# Project1.net
KiCad netlist of a schematic drawn in EAGLE
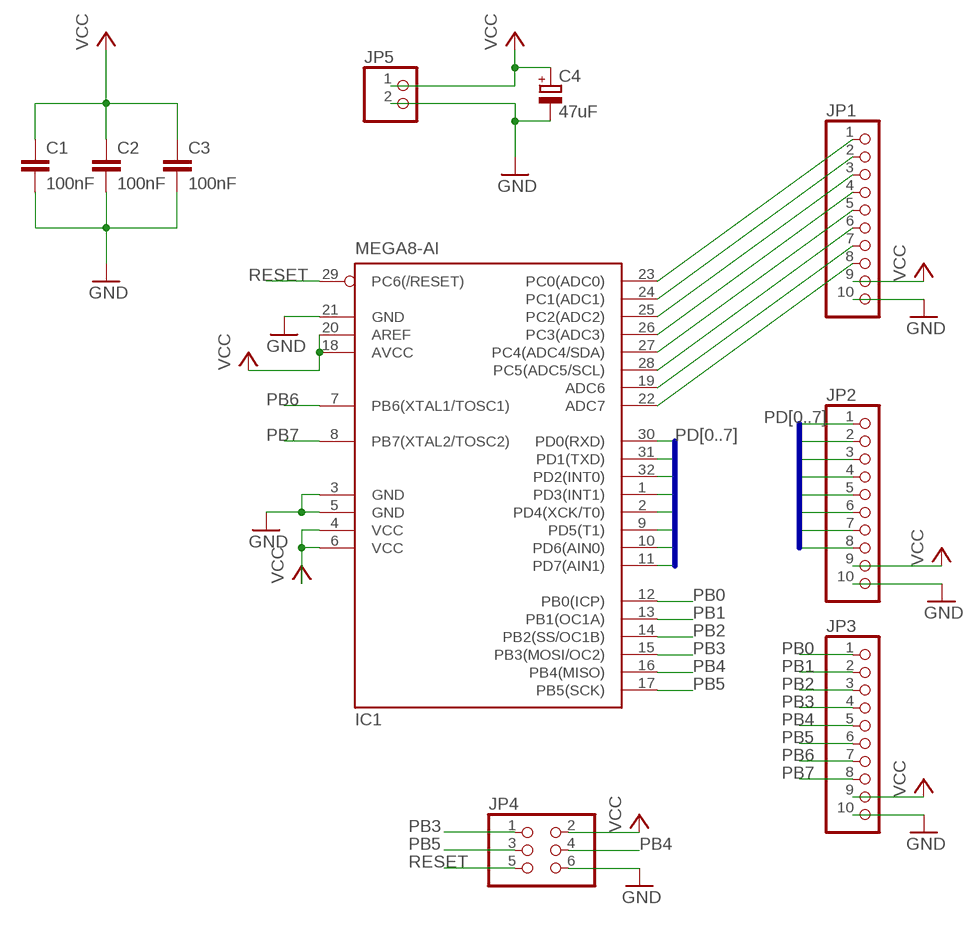
[diagram p0: schematic, sheet 1]

(export (version "E")
  (design (tool "Eeschema 10.0.6"))
  (components
    (comp (ref "C1")
      (value "100nF")
      (footprint "eagle-import:C0603")
      (libsource (lib "eagle-import") (part "C-EUC0603"))
    )
    (comp (ref "C2")
      (value "100nF")
      (footprint "eagle-import:C0603")
      (libsource (lib "eagle-import") (part "C-EUC0603"))
    )
    (comp (ref "C3")
      (value "100nF")
      (footprint "eagle-import:C0603")
      (libsource (lib "eagle-import") (part "C-EUC0603"))
    )
    (comp (ref "C4")
      (value "47uF")
      (footprint "eagle-import:E2,5-6")
      (libsource (lib "eagle-import") (part "CPOL-EUE2.5-6"))
    )
    (comp (ref "IC1")
      (value "MEGA8-AI")
      (footprint "eagle-import:TQFP32-08")
      (fields (field (name "MPN") "ATMEGA8-16AU"))
      (libsource (lib "eagle-import") (part "MEGA8-AI"))
    )
    (comp (ref "JP1")
      (value "PINHD-1X10")
      (footprint "eagle-import:1X10")
      (libsource (lib "eagle-import") (part "PINHD-1X10"))
    )
    (comp (ref "JP2")
      (value "PINHD-1X10")
      (footprint "eagle-import:1X10")
      (libsource (lib "eagle-import") (part "PINHD-1X10"))
    )
    (comp (ref "JP3")
      (value "PINHD-1X10")
      (footprint "eagle-import:1X10")
      (libsource (lib "eagle-import") (part "PINHD-1X10"))
    )
    (comp (ref "JP4")
      (value "PINHD-2X3")
      (footprint "eagle-import:2X03")
      (libsource (lib "eagle-import") (part "PINHD-2X3"))
    )
    (comp (ref "JP5")
      (value "PINHD-1X2")
      (footprint "eagle-import:1X02")
      (libsource (lib "eagle-import") (part "PINHD-1X2"))
    )
  )
  (nets
    (net (code "1") (name "/PB0") (class "Default")
      (node (ref "IC1") (pin "12") (pinfunction "PB0(ICP)_12") (pintype "bidirectional"))
      (node (ref "JP3") (pin "1") (pinfunction "1_1") (pintype "passive"))
    )
    (net (code "2") (name "/PB1") (class "Default")
      (node (ref "IC1") (pin "13") (pinfunction "PB1(OC1A)_13") (pintype "bidirectional"))
      (node (ref "JP3") (pin "2") (pinfunction "2_2") (pintype "passive"))
    )
    (net (code "3") (name "/PB2") (class "Default")
      (node (ref "IC1") (pin "14") (pinfunction "PB2(SS/OC1B)_14") (pintype "bidirectional"))
      (node (ref "JP3") (pin "3") (pinfunction "3_3") (pintype "passive"))
    )
    (net (code "4") (name "/PB3") (class "Default")
      (node (ref "IC1") (pin "15") (pinfunction "PB3(MOSI/OC2)_15") (pintype "bidirectional"))
      (node (ref "JP3") (pin "4") (pinfunction "4_4") (pintype "passive"))
      (node (ref "JP4") (pin "1") (pinfunction "1_1") (pintype "passive"))
    )
    (net (code "5") (name "/PB4") (class "Default")
      (node (ref "IC1") (pin "16") (pinfunction "PB4(MISO)_16") (pintype "bidirectional"))
      (node (ref "JP3") (pin "5") (pinfunction "5_5") (pintype "passive"))
      (node (ref "JP4") (pin "4") (pinfunction "4_4") (pintype "passive"))
    )
    (net (code "6") (name "/PB5") (class "Default")
      (node (ref "IC1") (pin "17") (pinfunction "PB5(SCK)_17") (pintype "bidirectional"))
      (node (ref "JP3") (pin "6") (pinfunction "6_6") (pintype "passive"))
      (node (ref "JP4") (pin "3") (pinfunction "3_3") (pintype "passive"))
    )
    (net (code "7") (name "/PB6") (class "Default")
      (node (ref "IC1") (pin "7") (pinfunction "PB6(XTAL1/TOSC1)_7") (pintype "bidirectional"))
      (node (ref "JP3") (pin "7") (pinfunction "7_7") (pintype "passive"))
    )
    (net (code "8") (name "/PB7") (class "Default")
      (node (ref "IC1") (pin "8") (pinfunction "PB7(XTAL2/TOSC2)_8") (pintype "bidirectional"))
      (node (ref "JP3") (pin "8") (pinfunction "8_8") (pintype "passive"))
    )
    (net (code "9") (name "/PD0") (class "Default")
      (node (ref "IC1") (pin "30") (pinfunction "PD0(RXD)_30") (pintype "bidirectional"))
      (node (ref "JP2") (pin "1") (pinfunction "1_1") (pintype "passive"))
    )
    (net (code "10") (name "/PD1") (class "Default")
      (node (ref "IC1") (pin "31") (pinfunction "PD1(TXD)_31") (pintype "bidirectional"))
      (node (ref "JP2") (pin "2") (pinfunction "2_2") (pintype "passive"))
    )
    (net (code "11") (name "/PD2") (class "Default")
      (node (ref "IC1") (pin "32") (pinfunction "PD2(INT0)_32") (pintype "bidirectional"))
      (node (ref "JP2") (pin "3") (pinfunction "3_3") (pintype "passive"))
    )
    (net (code "12") (name "/PD3") (class "Default")
      (node (ref "IC1") (pin "1") (pinfunction "PD3(INT1)_1") (pintype "bidirectional"))
      (node (ref "JP2") (pin "4") (pinfunction "4_4") (pintype "passive"))
    )
    (net (code "13") (name "/PD4") (class "Default")
      (node (ref "IC1") (pin "2") (pinfunction "PD4(XCK/T0)_2") (pintype "bidirectional"))
      (node (ref "JP2") (pin "5") (pinfunction "5_5") (pintype "passive"))
    )
    (net (code "14") (name "/PD5") (class "Default")
      (node (ref "IC1") (pin "9") (pinfunction "PD5(T1)_9") (pintype "bidirectional"))
      (node (ref "JP2") (pin "6") (pinfunction "6_6") (pintype "passive"))
    )
    (net (code "15") (name "/PD6") (class "Default")
      (node (ref "IC1") (pin "10") (pinfunction "PD6(AIN0)_10") (pintype "bidirectional"))
      (node (ref "JP2") (pin "7") (pinfunction "7_7") (pintype "passive"))
    )
    (net (code "16") (name "/PD7") (class "Default")
      (node (ref "IC1") (pin "11") (pinfunction "PD7(AIN1)_11") (pintype "bidirectional"))
      (node (ref "JP2") (pin "8") (pinfunction "8_8") (pintype "passive"))
    )
    (net (code "17") (name "/RESET") (class "Default")
      (node (ref "IC1") (pin "29") (pinfunction "PC6(/RESET)_29") (pintype "bidirectional"))
      (node (ref "JP4") (pin "5") (pinfunction "5_5") (pintype "passive"))
    )
    (net (code "18") (name "GND") (class "Default")
      (node (ref "C1") (pin "2") (pinfunction "2_2") (pintype "passive"))
      (node (ref "C2") (pin "2") (pinfunction "2_2") (pintype "passive"))
      (node (ref "C3") (pin "2") (pinfunction "2_2") (pintype "passive"))
      (node (ref "C4") (pin "-") (pinfunction "-_-") (pintype "passive"))
      (node (ref "IC1") (pin "21") (pinfunction "GND_21") (pintype "power_in"))
      (node (ref "IC1") (pin "3") (pinfunction "GND_3") (pintype "power_in"))
      (node (ref "IC1") (pin "5") (pinfunction "GND_5") (pintype "power_in"))
      (node (ref "JP1") (pin "10") (pinfunction "10_10") (pintype "passive"))
      (node (ref "JP2") (pin "10") (pinfunction "10_10") (pintype "passive"))
      (node (ref "JP3") (pin "10") (pinfunction "10_10") (pintype "passive"))
      (node (ref "JP4") (pin "6") (pinfunction "6_6") (pintype "passive"))
      (node (ref "JP5") (pin "2") (pinfunction "2_2") (pintype "passive"))
    )
    (net (code "19") (name "Net-(IC1-ADC6)") (class "Default")
      (node (ref "IC1") (pin "19") (pinfunction "ADC6_19") (pintype "bidirectional"))
      (node (ref "JP1") (pin "7") (pinfunction "7_7") (pintype "passive"))
    )
    (net (code "20") (name "Net-(IC1-ADC7)") (class "Default")
      (node (ref "IC1") (pin "22") (pinfunction "ADC7_22") (pintype "bidirectional"))
      (node (ref "JP1") (pin "8") (pinfunction "8_8") (pintype "passive"))
    )
    (net (code "21") (name "Net-(IC1-PC0(ADC0))") (class "Default")
      (node (ref "IC1") (pin "23") (pinfunction "PC0(ADC0)_23") (pintype "bidirectional"))
      (node (ref "JP1") (pin "1") (pinfunction "1_1") (pintype "passive"))
    )
    (net (code "22") (name "Net-(IC1-PC1(ADC1))") (class "Default")
      (node (ref "IC1") (pin "24") (pinfunction "PC1(ADC1)_24") (pintype "bidirectional"))
      (node (ref "JP1") (pin "2") (pinfunction "2_2") (pintype "passive"))
    )
    (net (code "23") (name "Net-(IC1-PC2(ADC2))") (class "Default")
      (node (ref "IC1") (pin "25") (pinfunction "PC2(ADC2)_25") (pintype "bidirectional"))
      (node (ref "JP1") (pin "3") (pinfunction "3_3") (pintype "passive"))
    )
    (net (code "24") (name "Net-(IC1-PC3(ADC3))") (class "Default")
      (node (ref "IC1") (pin "26") (pinfunction "PC3(ADC3)_26") (pintype "bidirectional"))
      (node (ref "JP1") (pin "4") (pinfunction "4_4") (pintype "passive"))
    )
    (net (code "25") (name "Net-(IC1-PC4(ADC4{slash}SDA))") (class "Default")
      (node (ref "IC1") (pin "27") (pinfunction "PC4(ADC4/SDA)_27") (pintype "bidirectional"))
      (node (ref "JP1") (pin "5") (pinfunction "5_5") (pintype "passive"))
    )
    (net (code "26") (name "Net-(IC1-PC5(ADC5{slash}SCL))") (class "Default")
      (node (ref "IC1") (pin "28") (pinfunction "PC5(ADC5/SCL)_28") (pintype "bidirectional"))
      (node (ref "JP1") (pin "6") (pinfunction "6_6") (pintype "passive"))
    )
    (net (code "27") (name "VCC") (class "Default")
      (node (ref "C1") (pin "1") (pinfunction "1_1") (pintype "passive"))
      (node (ref "C2") (pin "1") (pinfunction "1_1") (pintype "passive"))
      (node (ref "C3") (pin "1") (pinfunction "1_1") (pintype "passive"))
      (node (ref "C4") (pin "+") (pinfunction "+_+") (pintype "passive"))
      (node (ref "IC1") (pin "18") (pinfunction "AVCC_18") (pintype "power_in"))
      (node (ref "IC1") (pin "20") (pinfunction "AREF_20") (pintype "passive"))
      (node (ref "IC1") (pin "4") (pinfunction "VCC_4") (pintype "power_in"))
      (node (ref "IC1") (pin "6") (pinfunction "VCC_6") (pintype "power_in"))
      (node (ref "JP1") (pin "9") (pinfunction "9_9") (pintype "passive"))
      (node (ref "JP2") (pin "9") (pinfunction "9_9") (pintype "passive"))
      (node (ref "JP3") (pin "9") (pinfunction "9_9") (pintype "passive"))
      (node (ref "JP4") (pin "2") (pinfunction "2_2") (pintype "passive"))
      (node (ref "JP5") (pin "1") (pinfunction "1_1") (pintype "passive"))
    )
  )
)
